# board_led.net
KiCad netlist of a schematic drawn in EAGLE
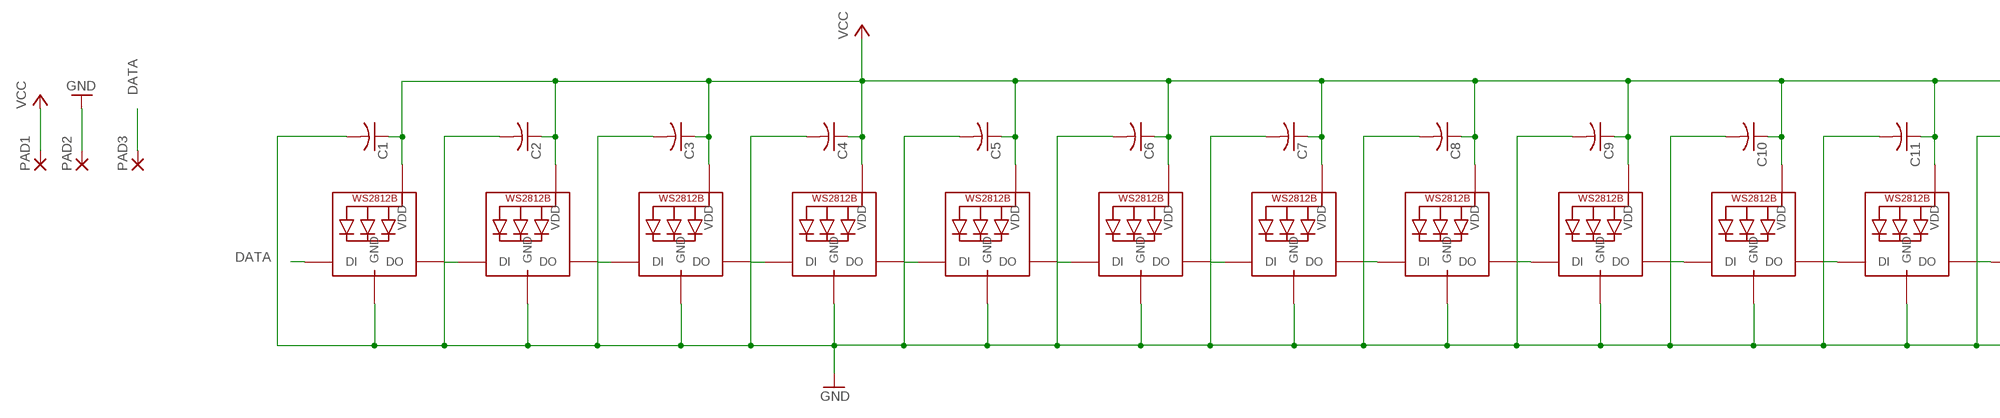
[diagram p0: schematic, sheet 1, part 1 of 2]
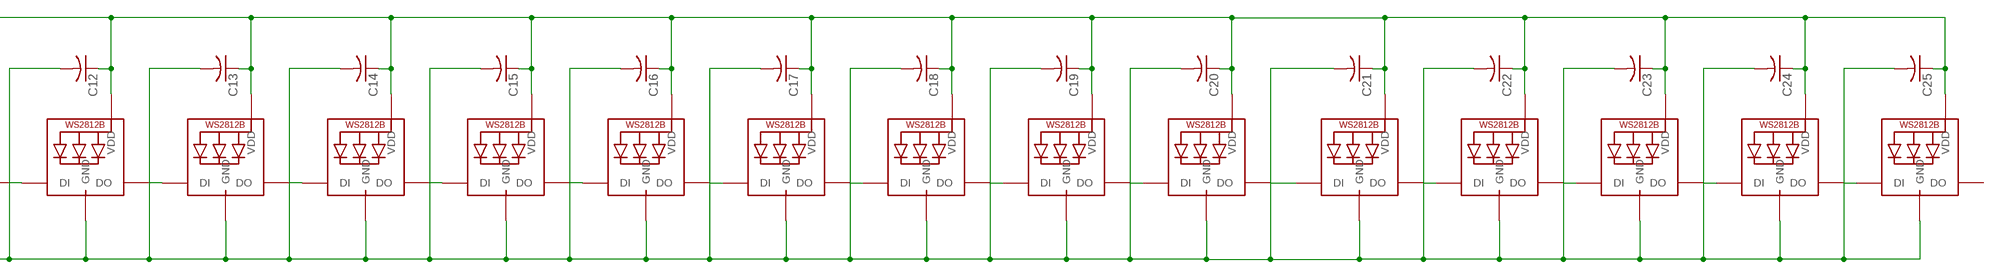
[diagram p1: schematic, sheet 1, part 2 of 2]

(export (version "E")
  (design (tool "Eeschema 10.0.6"))
  (components
    (comp (ref "C1")
      (value "C-USC0805")
      (footprint "eagle-import:C0805")
      (libsource (lib "eagle-import") (part "C-USC0805"))
    )
    (comp (ref "C2")
      (value "C-USC0805")
      (footprint "eagle-import:C0805")
      (libsource (lib "eagle-import") (part "C-USC0805"))
    )
    (comp (ref "C3")
      (value "C-USC0805")
      (footprint "eagle-import:C0805")
      (libsource (lib "eagle-import") (part "C-USC0805"))
    )
    (comp (ref "C4")
      (value "C-USC0805")
      (footprint "eagle-import:C0805")
      (libsource (lib "eagle-import") (part "C-USC0805"))
    )
    (comp (ref "C5")
      (value "C-USC0805")
      (footprint "eagle-import:C0805")
      (libsource (lib "eagle-import") (part "C-USC0805"))
    )
    (comp (ref "C6")
      (value "C-USC0805")
      (footprint "eagle-import:C0805")
      (libsource (lib "eagle-import") (part "C-USC0805"))
    )
    (comp (ref "C7")
      (value "C-USC0805")
      (footprint "eagle-import:C0805")
      (libsource (lib "eagle-import") (part "C-USC0805"))
    )
    (comp (ref "C8")
      (value "C-USC0805")
      (footprint "eagle-import:C0805")
      (libsource (lib "eagle-import") (part "C-USC0805"))
    )
    (comp (ref "C9")
      (value "C-USC0805")
      (footprint "eagle-import:C0805")
      (libsource (lib "eagle-import") (part "C-USC0805"))
    )
    (comp (ref "C10")
      (value "C-USC0805")
      (footprint "eagle-import:C0805")
      (libsource (lib "eagle-import") (part "C-USC0805"))
    )
    (comp (ref "C11")
      (value "C-USC0805")
      (footprint "eagle-import:C0805")
      (libsource (lib "eagle-import") (part "C-USC0805"))
    )
    (comp (ref "C12")
      (value "C-USC0805")
      (footprint "eagle-import:C0805")
      (libsource (lib "eagle-import") (part "C-USC0805"))
    )
    (comp (ref "C13")
      (value "C-USC0805")
      (footprint "eagle-import:C0805")
      (libsource (lib "eagle-import") (part "C-USC0805"))
    )
    (comp (ref "C14")
      (value "C-USC0805")
      (footprint "eagle-import:C0805")
      (libsource (lib "eagle-import") (part "C-USC0805"))
    )
    (comp (ref "C15")
      (value "C-USC0805")
      (footprint "eagle-import:C0805")
      (libsource (lib "eagle-import") (part "C-USC0805"))
    )
    (comp (ref "C16")
      (value "C-USC0805")
      (footprint "eagle-import:C0805")
      (libsource (lib "eagle-import") (part "C-USC0805"))
    )
    (comp (ref "C17")
      (value "C-USC0805")
      (footprint "eagle-import:C0805")
      (libsource (lib "eagle-import") (part "C-USC0805"))
    )
    (comp (ref "C18")
      (value "C-USC0805")
      (footprint "eagle-import:C0805")
      (libsource (lib "eagle-import") (part "C-USC0805"))
    )
    (comp (ref "C19")
      (value "C-USC0805")
      (footprint "eagle-import:C0805")
      (libsource (lib "eagle-import") (part "C-USC0805"))
    )
    (comp (ref "C20")
      (value "C-USC0805")
      (footprint "eagle-import:C0805")
      (libsource (lib "eagle-import") (part "C-USC0805"))
    )
    (comp (ref "C21")
      (value "C-USC0805")
      (footprint "eagle-import:C0805")
      (libsource (lib "eagle-import") (part "C-USC0805"))
    )
    (comp (ref "C22")
      (value "C-USC0805")
      (footprint "eagle-import:C0805")
      (libsource (lib "eagle-import") (part "C-USC0805"))
    )
    (comp (ref "C23")
      (value "C-USC0805")
      (footprint "eagle-import:C0805")
      (libsource (lib "eagle-import") (part "C-USC0805"))
    )
    (comp (ref "C24")
      (value "C-USC0805")
      (footprint "eagle-import:C0805")
      (libsource (lib "eagle-import") (part "C-USC0805"))
    )
    (comp (ref "C25")
      (value "C-USC0805")
      (footprint "eagle-import:C0805")
      (libsource (lib "eagle-import") (part "C-USC0805"))
    )
    (comp (ref "LED1")
      (value "WS2812B5050")
      (footprint "eagle-import:WS2812B")
      (libsource (lib "eagle-import") (part "WS2812B5050"))
    )
    (comp (ref "LED2")
      (value "WS2812B5050")
      (footprint "eagle-import:WS2812B")
      (libsource (lib "eagle-import") (part "WS2812B5050"))
    )
    (comp (ref "LED3")
      (value "WS2812B5050")
      (footprint "eagle-import:WS2812B")
      (libsource (lib "eagle-import") (part "WS2812B5050"))
    )
    (comp (ref "LED4")
      (value "WS2812B5050")
      (footprint "eagle-import:WS2812B")
      (libsource (lib "eagle-import") (part "WS2812B5050"))
    )
    (comp (ref "LED5")
      (value "WS2812B5050")
      (footprint "eagle-import:WS2812B")
      (libsource (lib "eagle-import") (part "WS2812B5050"))
    )
    (comp (ref "LED6")
      (value "WS2812B5050")
      (footprint "eagle-import:WS2812B")
      (libsource (lib "eagle-import") (part "WS2812B5050"))
    )
    (comp (ref "LED7")
      (value "WS2812B5050")
      (footprint "eagle-import:WS2812B")
      (libsource (lib "eagle-import") (part "WS2812B5050"))
    )
    (comp (ref "LED8")
      (value "WS2812B5050")
      (footprint "eagle-import:WS2812B")
      (libsource (lib "eagle-import") (part "WS2812B5050"))
    )
    (comp (ref "LED9")
      (value "WS2812B5050")
      (footprint "eagle-import:WS2812B")
      (libsource (lib "eagle-import") (part "WS2812B5050"))
    )
    (comp (ref "LED10")
      (value "WS2812B5050")
      (footprint "eagle-import:WS2812B")
      (libsource (lib "eagle-import") (part "WS2812B5050"))
    )
    (comp (ref "LED11")
      (value "WS2812B5050")
      (footprint "eagle-import:WS2812B")
      (libsource (lib "eagle-import") (part "WS2812B5050"))
    )
    (comp (ref "LED12")
      (value "WS2812B5050")
      (footprint "eagle-import:WS2812B")
      (libsource (lib "eagle-import") (part "WS2812B5050"))
    )
    (comp (ref "LED13")
      (value "WS2812B5050")
      (footprint "eagle-import:WS2812B")
      (libsource (lib "eagle-import") (part "WS2812B5050"))
    )
    (comp (ref "LED14")
      (value "WS2812B5050")
      (footprint "eagle-import:WS2812B")
      (libsource (lib "eagle-import") (part "WS2812B5050"))
    )
    (comp (ref "LED15")
      (value "WS2812B5050")
      (footprint "eagle-import:WS2812B")
      (libsource (lib "eagle-import") (part "WS2812B5050"))
    )
    (comp (ref "LED16")
      (value "WS2812B5050")
      (footprint "eagle-import:WS2812B")
      (libsource (lib "eagle-import") (part "WS2812B5050"))
    )
    (comp (ref "LED17")
      (value "WS2812B5050")
      (footprint "eagle-import:WS2812B")
      (libsource (lib "eagle-import") (part "WS2812B5050"))
    )
    (comp (ref "LED18")
      (value "WS2812B5050")
      (footprint "eagle-import:WS2812B")
      (libsource (lib "eagle-import") (part "WS2812B5050"))
    )
    (comp (ref "LED19")
      (value "WS2812B5050")
      (footprint "eagle-import:WS2812B")
      (libsource (lib "eagle-import") (part "WS2812B5050"))
    )
    (comp (ref "LED20")
      (value "WS2812B5050")
      (footprint "eagle-import:WS2812B")
      (libsource (lib "eagle-import") (part "WS2812B5050"))
    )
    (comp (ref "LED21")
      (value "WS2812B5050")
      (footprint "eagle-import:WS2812B")
      (libsource (lib "eagle-import") (part "WS2812B5050"))
    )
    (comp (ref "LED22")
      (value "WS2812B5050")
      (footprint "eagle-import:WS2812B")
      (libsource (lib "eagle-import") (part "WS2812B5050"))
    )
    (comp (ref "LED23")
      (value "WS2812B5050")
      (footprint "eagle-import:WS2812B")
      (libsource (lib "eagle-import") (part "WS2812B5050"))
    )
    (comp (ref "LED24")
      (value "WS2812B5050")
      (footprint "eagle-import:WS2812B")
      (libsource (lib "eagle-import") (part "WS2812B5050"))
    )
    (comp (ref "LED25")
      (value "WS2812B5050")
      (footprint "eagle-import:WS2812B")
      (libsource (lib "eagle-import") (part "WS2812B5050"))
    )
    (comp (ref "PAD1")
      (value "SMD5")
      (footprint "eagle-import:SMD2,54-5,08")
      (libsource (lib "eagle-import") (part "SMD5"))
    )
    (comp (ref "PAD2")
      (value "SMD5")
      (footprint "eagle-import:SMD2,54-5,08")
      (libsource (lib "eagle-import") (part "SMD5"))
    )
    (comp (ref "PAD3")
      (value "SMD5")
      (footprint "eagle-import:SMD2,54-5,08")
      (libsource (lib "eagle-import") (part "SMD5"))
    )
  )
  (nets
    (net (code "1") (name "/DATA") (class "Default")
      (node (ref "LED1") (pin "4-DIN") (pinfunction "DI_4-DIN") (pintype "input"))
      (node (ref "PAD3") (pin "1") (pinfunction "P_1") (pintype "passive"))
    )
    (net (code "2") (name "GND") (class "Default")
      (node (ref "C1") (pin "2") (pinfunction "2_2") (pintype "passive"))
      (node (ref "C10") (pin "2") (pinfunction "2_2") (pintype "passive"))
      (node (ref "C11") (pin "2") (pinfunction "2_2") (pintype "passive"))
      (node (ref "C12") (pin "2") (pinfunction "2_2") (pintype "passive"))
      (node (ref "C13") (pin "2") (pinfunction "2_2") (pintype "passive"))
      (node (ref "C14") (pin "2") (pinfunction "2_2") (pintype "passive"))
      (node (ref "C15") (pin "2") (pinfunction "2_2") (pintype "passive"))
      (node (ref "C16") (pin "2") (pinfunction "2_2") (pintype "passive"))
      (node (ref "C17") (pin "2") (pinfunction "2_2") (pintype "passive"))
      (node (ref "C18") (pin "2") (pinfunction "2_2") (pintype "passive"))
      (node (ref "C19") (pin "2") (pinfunction "2_2") (pintype "passive"))
      (node (ref "C2") (pin "2") (pinfunction "2_2") (pintype "passive"))
      (node (ref "C20") (pin "2") (pinfunction "2_2") (pintype "passive"))
      (node (ref "C21") (pin "2") (pinfunction "2_2") (pintype "passive"))
      (node (ref "C22") (pin "2") (pinfunction "2_2") (pintype "passive"))
      (node (ref "C23") (pin "2") (pinfunction "2_2") (pintype "passive"))
      (node (ref "C24") (pin "2") (pinfunction "2_2") (pintype "passive"))
      (node (ref "C25") (pin "2") (pinfunction "2_2") (pintype "passive"))
      (node (ref "C3") (pin "2") (pinfunction "2_2") (pintype "passive"))
      (node (ref "C4") (pin "2") (pinfunction "2_2") (pintype "passive"))
      (node (ref "C5") (pin "2") (pinfunction "2_2") (pintype "passive"))
      (node (ref "C6") (pin "2") (pinfunction "2_2") (pintype "passive"))
      (node (ref "C7") (pin "2") (pinfunction "2_2") (pintype "passive"))
      (node (ref "C8") (pin "2") (pinfunction "2_2") (pintype "passive"))
      (node (ref "C9") (pin "2") (pinfunction "2_2") (pintype "passive"))
      (node (ref "LED1") (pin "3-GND") (pinfunction "GND_3-GND") (pintype "power_in"))
      (node (ref "LED10") (pin "3-GND") (pinfunction "GND_3-GND") (pintype "power_in"))
      (node (ref "LED11") (pin "3-GND") (pinfunction "GND_3-GND") (pintype "power_in"))
      (node (ref "LED12") (pin "3-GND") (pinfunction "GND_3-GND") (pintype "power_in"))
      (node (ref "LED13") (pin "3-GND") (pinfunction "GND_3-GND") (pintype "power_in"))
      (node (ref "LED14") (pin "3-GND") (pinfunction "GND_3-GND") (pintype "power_in"))
      (node (ref "LED15") (pin "3-GND") (pinfunction "GND_3-GND") (pintype "power_in"))
      (node (ref "LED16") (pin "3-GND") (pinfunction "GND_3-GND") (pintype "power_in"))
      (node (ref "LED17") (pin "3-GND") (pinfunction "GND_3-GND") (pintype "power_in"))
      (node (ref "LED18") (pin "3-GND") (pinfunction "GND_3-GND") (pintype "power_in"))
      (node (ref "LED19") (pin "3-GND") (pinfunction "GND_3-GND") (pintype "power_in"))
      (node (ref "LED2") (pin "3-GND") (pinfunction "GND_3-GND") (pintype "power_in"))
      (node (ref "LED20") (pin "3-GND") (pinfunction "GND_3-GND") (pintype "power_in"))
      (node (ref "LED21") (pin "3-GND") (pinfunction "GND_3-GND") (pintype "power_in"))
      (node (ref "LED22") (pin "3-GND") (pinfunction "GND_3-GND") (pintype "power_in"))
      (node (ref "LED23") (pin "3-GND") (pinfunction "GND_3-GND") (pintype "power_in"))
      (node (ref "LED24") (pin "3-GND") (pinfunction "GND_3-GND") (pintype "power_in"))
      (node (ref "LED25") (pin "3-GND") (pinfunction "GND_3-GND") (pintype "power_in"))
      (node (ref "LED3") (pin "3-GND") (pinfunction "GND_3-GND") (pintype "power_in"))
      (node (ref "LED4") (pin "3-GND") (pinfunction "GND_3-GND") (pintype "power_in"))
      (node (ref "LED5") (pin "3-GND") (pinfunction "GND_3-GND") (pintype "power_in"))
      (node (ref "LED6") (pin "3-GND") (pinfunction "GND_3-GND") (pintype "power_in"))
      (node (ref "LED7") (pin "3-GND") (pinfunction "GND_3-GND") (pintype "power_in"))
      (node (ref "LED8") (pin "3-GND") (pinfunction "GND_3-GND") (pintype "power_in"))
      (node (ref "LED9") (pin "3-GND") (pinfunction "GND_3-GND") (pintype "power_in"))
      (node (ref "PAD2") (pin "1") (pinfunction "P_1") (pintype "passive"))
    )
    (net (code "3") (name "Net-(LED1-DO)") (class "Default")
      (node (ref "LED1") (pin "2-DOUT") (pinfunction "DO_2-DOUT") (pintype "output"))
      (node (ref "LED2") (pin "4-DIN") (pinfunction "DI_4-DIN") (pintype "input"))
    )
    (net (code "4") (name "Net-(LED2-DO)") (class "Default")
      (node (ref "LED2") (pin "2-DOUT") (pinfunction "DO_2-DOUT") (pintype "output"))
      (node (ref "LED3") (pin "4-DIN") (pinfunction "DI_4-DIN") (pintype "input"))
    )
    (net (code "5") (name "Net-(LED3-DO)") (class "Default")
      (node (ref "LED3") (pin "2-DOUT") (pinfunction "DO_2-DOUT") (pintype "output"))
      (node (ref "LED4") (pin "4-DIN") (pinfunction "DI_4-DIN") (pintype "input"))
    )
    (net (code "6") (name "Net-(LED4-DO)") (class "Default")
      (node (ref "LED4") (pin "2-DOUT") (pinfunction "DO_2-DOUT") (pintype "output"))
      (node (ref "LED5") (pin "4-DIN") (pinfunction "DI_4-DIN") (pintype "input"))
    )
    (net (code "7") (name "Net-(LED5-DO)") (class "Default")
      (node (ref "LED5") (pin "2-DOUT") (pinfunction "DO_2-DOUT") (pintype "output"))
      (node (ref "LED6") (pin "4-DIN") (pinfunction "DI_4-DIN") (pintype "input"))
    )
    (net (code "8") (name "Net-(LED6-DO)") (class "Default")
      (node (ref "LED6") (pin "2-DOUT") (pinfunction "DO_2-DOUT") (pintype "output"))
      (node (ref "LED7") (pin "4-DIN") (pinfunction "DI_4-DIN") (pintype "input"))
    )
    (net (code "9") (name "Net-(LED7-DO)") (class "Default")
      (node (ref "LED7") (pin "2-DOUT") (pinfunction "DO_2-DOUT") (pintype "output"))
      (node (ref "LED8") (pin "4-DIN") (pinfunction "DI_4-DIN") (pintype "input"))
    )
    (net (code "10") (name "Net-(LED8-DO)") (class "Default")
      (node (ref "LED8") (pin "2-DOUT") (pinfunction "DO_2-DOUT") (pintype "output"))
      (node (ref "LED9") (pin "4-DIN") (pinfunction "DI_4-DIN") (pintype "input"))
    )
    (net (code "11") (name "Net-(LED10-DI)") (class "Default")
      (node (ref "LED10") (pin "4-DIN") (pinfunction "DI_4-DIN") (pintype "input"))
      (node (ref "LED9") (pin "2-DOUT") (pinfunction "DO_2-DOUT") (pintype "output"))
    )
    (net (code "12") (name "Net-(LED10-DO)") (class "Default")
      (node (ref "LED10") (pin "2-DOUT") (pinfunction "DO_2-DOUT") (pintype "output"))
      (node (ref "LED11") (pin "4-DIN") (pinfunction "DI_4-DIN") (pintype "input"))
    )
    (net (code "13") (name "Net-(LED11-DO)") (class "Default")
      (node (ref "LED11") (pin "2-DOUT") (pinfunction "DO_2-DOUT") (pintype "output"))
      (node (ref "LED12") (pin "4-DIN") (pinfunction "DI_4-DIN") (pintype "input"))
    )
    (net (code "14") (name "Net-(LED12-DO)") (class "Default")
      (node (ref "LED12") (pin "2-DOUT") (pinfunction "DO_2-DOUT") (pintype "output"))
      (node (ref "LED13") (pin "4-DIN") (pinfunction "DI_4-DIN") (pintype "input"))
    )
    (net (code "15") (name "Net-(LED13-DO)") (class "Default")
      (node (ref "LED13") (pin "2-DOUT") (pinfunction "DO_2-DOUT") (pintype "output"))
      (node (ref "LED14") (pin "4-DIN") (pinfunction "DI_4-DIN") (pintype "input"))
    )
    (net (code "16") (name "Net-(LED14-DO)") (class "Default")
      (node (ref "LED14") (pin "2-DOUT") (pinfunction "DO_2-DOUT") (pintype "output"))
      (node (ref "LED15") (pin "4-DIN") (pinfunction "DI_4-DIN") (pintype "input"))
    )
    (net (code "17") (name "Net-(LED15-DO)") (class "Default")
      (node (ref "LED15") (pin "2-DOUT") (pinfunction "DO_2-DOUT") (pintype "output"))
      (node (ref "LED16") (pin "4-DIN") (pinfunction "DI_4-DIN") (pintype "input"))
    )
    (net (code "18") (name "Net-(LED16-DO)") (class "Default")
      (node (ref "LED16") (pin "2-DOUT") (pinfunction "DO_2-DOUT") (pintype "output"))
      (node (ref "LED17") (pin "4-DIN") (pinfunction "DI_4-DIN") (pintype "input"))
    )
    (net (code "19") (name "Net-(LED17-DO)") (class "Default")
      (node (ref "LED17") (pin "2-DOUT") (pinfunction "DO_2-DOUT") (pintype "output"))
      (node (ref "LED18") (pin "4-DIN") (pinfunction "DI_4-DIN") (pintype "input"))
    )
    (net (code "20") (name "Net-(LED18-DO)") (class "Default")
      (node (ref "LED18") (pin "2-DOUT") (pinfunction "DO_2-DOUT") (pintype "output"))
      (node (ref "LED19") (pin "4-DIN") (pinfunction "DI_4-DIN") (pintype "input"))
    )
    (net (code "21") (name "Net-(LED19-DO)") (class "Default")
      (node (ref "LED19") (pin "2-DOUT") (pinfunction "DO_2-DOUT") (pintype "output"))
      (node (ref "LED20") (pin "4-DIN") (pinfunction "DI_4-DIN") (pintype "input"))
    )
    (net (code "22") (name "Net-(LED20-DO)") (class "Default")
      (node (ref "LED20") (pin "2-DOUT") (pinfunction "DO_2-DOUT") (pintype "output"))
      (node (ref "LED21") (pin "4-DIN") (pinfunction "DI_4-DIN") (pintype "input"))
    )
    (net (code "23") (name "Net-(LED21-DO)") (class "Default")
      (node (ref "LED21") (pin "2-DOUT") (pinfunction "DO_2-DOUT") (pintype "output"))
      (node (ref "LED22") (pin "4-DIN") (pinfunction "DI_4-DIN") (pintype "input"))
    )
    (net (code "24") (name "Net-(LED22-DO)") (class "Default")
      (node (ref "LED22") (pin "2-DOUT") (pinfunction "DO_2-DOUT") (pintype "output"))
      (node (ref "LED23") (pin "4-DIN") (pinfunction "DI_4-DIN") (pintype "input"))
    )
    (net (code "25") (name "Net-(LED23-DO)") (class "Default")
      (node (ref "LED23") (pin "2-DOUT") (pinfunction "DO_2-DOUT") (pintype "output"))
      (node (ref "LED24") (pin "4-DIN") (pinfunction "DI_4-DIN") (pintype "input"))
    )
    (net (code "26") (name "Net-(LED24-DO)") (class "Default")
      (node (ref "LED24") (pin "2-DOUT") (pinfunction "DO_2-DOUT") (pintype "output"))
      (node (ref "LED25") (pin "4-DIN") (pinfunction "DI_4-DIN") (pintype "input"))
    )
    (net (code "27") (name "VCC") (class "Default")
      (node (ref "C1") (pin "1") (pinfunction "1_1") (pintype "passive"))
      (node (ref "C10") (pin "1") (pinfunction "1_1") (pintype "passive"))
      (node (ref "C11") (pin "1") (pinfunction "1_1") (pintype "passive"))
      (node (ref "C12") (pin "1") (pinfunction "1_1") (pintype "passive"))
      (node (ref "C13") (pin "1") (pinfunction "1_1") (pintype "passive"))
      (node (ref "C14") (pin "1") (pinfunction "1_1") (pintype "passive"))
      (node (ref "C15") (pin "1") (pinfunction "1_1") (pintype "passive"))
      (node (ref "C16") (pin "1") (pinfunction "1_1") (pintype "passive"))
      (node (ref "C17") (pin "1") (pinfunction "1_1") (pintype "passive"))
      (node (ref "C18") (pin "1") (pinfunction "1_1") (pintype "passive"))
      (node (ref "C19") (pin "1") (pinfunction "1_1") (pintype "passive"))
      (node (ref "C2") (pin "1") (pinfunction "1_1") (pintype "passive"))
      (node (ref "C20") (pin "1") (pinfunction "1_1") (pintype "passive"))
      (node (ref "C21") (pin "1") (pinfunction "1_1") (pintype "passive"))
      (node (ref "C22") (pin "1") (pinfunction "1_1") (pintype "passive"))
      (node (ref "C23") (pin "1") (pinfunction "1_1") (pintype "passive"))
      (node (ref "C24") (pin "1") (pinfunction "1_1") (pintype "passive"))
      (node (ref "C25") (pin "1") (pinfunction "1_1") (pintype "passive"))
      (node (ref "C3") (pin "1") (pinfunction "1_1") (pintype "passive"))
      (node (ref "C4") (pin "1") (pinfunction "1_1") (pintype "passive"))
      (node (ref "C5") (pin "1") (pinfunction "1_1") (pintype "passive"))
      (node (ref "C6") (pin "1") (pinfunction "1_1") (pintype "passive"))
      (node (ref "C7") (pin "1") (pinfunction "1_1") (pintype "passive"))
      (node (ref "C8") (pin "1") (pinfunction "1_1") (pintype "passive"))
      (node (ref "C9") (pin "1") (pinfunction "1_1") (pintype "passive"))
      (node (ref "LED1") (pin "1-VDD") (pinfunction "VDD_1-VDD") (pintype "power_in"))
      (node (ref "LED10") (pin "1-VDD") (pinfunction "VDD_1-VDD") (pintype "power_in"))
      (node (ref "LED11") (pin "1-VDD") (pinfunction "VDD_1-VDD") (pintype "power_in"))
      (node (ref "LED12") (pin "1-VDD") (pinfunction "VDD_1-VDD") (pintype "power_in"))
      (node (ref "LED13") (pin "1-VDD") (pinfunction "VDD_1-VDD") (pintype "power_in"))
      (node (ref "LED14") (pin "1-VDD") (pinfunction "VDD_1-VDD") (pintype "power_in"))
      (node (ref "LED15") (pin "1-VDD") (pinfunction "VDD_1-VDD") (pintype "power_in"))
      (node (ref "LED16") (pin "1-VDD") (pinfunction "VDD_1-VDD") (pintype "power_in"))
      (node (ref "LED17") (pin "1-VDD") (pinfunction "VDD_1-VDD") (pintype "power_in"))
      (node (ref "LED18") (pin "1-VDD") (pinfunction "VDD_1-VDD") (pintype "power_in"))
      (node (ref "LED19") (pin "1-VDD") (pinfunction "VDD_1-VDD") (pintype "power_in"))
      (node (ref "LED2") (pin "1-VDD") (pinfunction "VDD_1-VDD") (pintype "power_in"))
      (node (ref "LED20") (pin "1-VDD") (pinfunction "VDD_1-VDD") (pintype "power_in"))
      (node (ref "LED21") (pin "1-VDD") (pinfunction "VDD_1-VDD") (pintype "power_in"))
      (node (ref "LED22") (pin "1-VDD") (pinfunction "VDD_1-VDD") (pintype "power_in"))
      (node (ref "LED23") (pin "1-VDD") (pinfunction "VDD_1-VDD") (pintype "power_in"))
      (node (ref "LED24") (pin "1-VDD") (pinfunction "VDD_1-VDD") (pintype "power_in"))
      (node (ref "LED25") (pin "1-VDD") (pinfunction "VDD_1-VDD") (pintype "power_in"))
      (node (ref "LED3") (pin "1-VDD") (pinfunction "VDD_1-VDD") (pintype "power_in"))
      (node (ref "LED4") (pin "1-VDD") (pinfunction "VDD_1-VDD") (pintype "power_in"))
      (node (ref "LED5") (pin "1-VDD") (pinfunction "VDD_1-VDD") (pintype "power_in"))
      (node (ref "LED6") (pin "1-VDD") (pinfunction "VDD_1-VDD") (pintype "power_in"))
      (node (ref "LED7") (pin "1-VDD") (pinfunction "VDD_1-VDD") (pintype "power_in"))
      (node (ref "LED8") (pin "1-VDD") (pinfunction "VDD_1-VDD") (pintype "power_in"))
      (node (ref "LED9") (pin "1-VDD") (pinfunction "VDD_1-VDD") (pintype "power_in"))
      (node (ref "PAD1") (pin "1") (pinfunction "P_1") (pintype "passive"))
    )
    (net (code "28") (name "unconnected-(LED25-DO-Pad2-DOUT)") (class "Default")
      (node (ref "LED25") (pin "2-DOUT") (pinfunction "DO_2-DOUT") (pintype "output"))
    )
  )
)
